# TopPanelV3_2.net
KiCad netlist of a schematic drawn in EAGLE
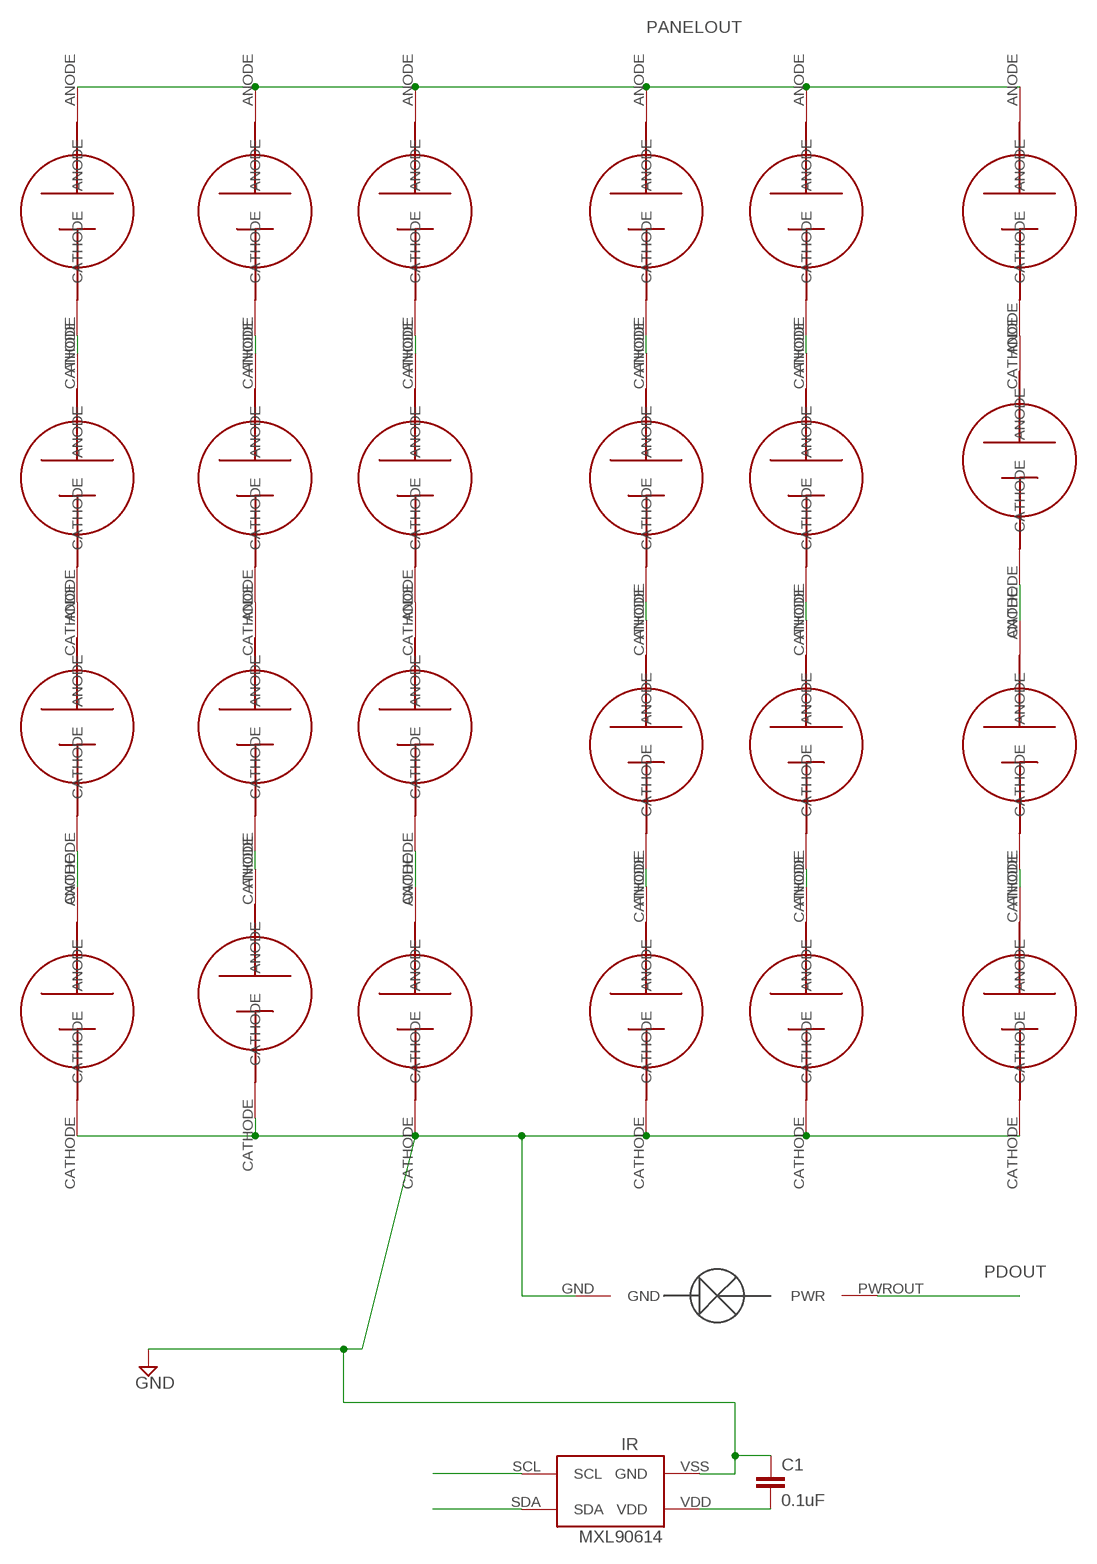
[diagram p0: schematic, sheet 1]

(export (version "E")
  (design (tool "Eeschema 10.0.6"))
  (components
    (comp (ref "1A")
      (value "SOLARCELL")
      (footprint "eagle-import:SOLARCELL")
      (libsource (lib "eagle-import") (part "SOLARCELL"))
    )
    (comp (ref "1B")
      (value "SOLARCELL")
      (footprint "eagle-import:SOLARCELL")
      (libsource (lib "eagle-import") (part "SOLARCELL"))
    )
    (comp (ref "1C")
      (value "SOLARCELL")
      (footprint "eagle-import:SOLARCELL")
      (libsource (lib "eagle-import") (part "SOLARCELL"))
    )
    (comp (ref "1D")
      (value "SOLARCELL")
      (footprint "eagle-import:SOLARCELL")
      (libsource (lib "eagle-import") (part "SOLARCELL"))
    )
    (comp (ref "2A")
      (value "SOLARCELL")
      (footprint "eagle-import:SOLARCELL")
      (libsource (lib "eagle-import") (part "SOLARCELL"))
    )
    (comp (ref "2B")
      (value "SOLARCELL")
      (footprint "eagle-import:SOLARCELL")
      (libsource (lib "eagle-import") (part "SOLARCELL"))
    )
    (comp (ref "2C")
      (value "SOLARCELL")
      (footprint "eagle-import:SOLARCELL")
      (libsource (lib "eagle-import") (part "SOLARCELL"))
    )
    (comp (ref "2D")
      (value "SOLARCELL")
      (footprint "eagle-import:SOLARCELL")
      (libsource (lib "eagle-import") (part "SOLARCELL"))
    )
    (comp (ref "3A")
      (value "SOLARCELL")
      (footprint "eagle-import:SOLARCELL")
      (libsource (lib "eagle-import") (part "SOLARCELL"))
    )
    (comp (ref "3B")
      (value "SOLARCELL")
      (footprint "eagle-import:SOLARCELL")
      (libsource (lib "eagle-import") (part "SOLARCELL"))
    )
    (comp (ref "3C")
      (value "SOLARCELL")
      (footprint "eagle-import:SOLARCELL")
      (libsource (lib "eagle-import") (part "SOLARCELL"))
    )
    (comp (ref "3D")
      (value "SOLARCELL")
      (footprint "eagle-import:SOLARCELL")
      (libsource (lib "eagle-import") (part "SOLARCELL"))
    )
    (comp (ref "4A")
      (value "SOLARCELL")
      (footprint "eagle-import:SOLARCELL")
      (libsource (lib "eagle-import") (part "SOLARCELL"))
    )
    (comp (ref "4B")
      (value "SOLARCELL")
      (footprint "eagle-import:SOLARCELL")
      (libsource (lib "eagle-import") (part "SOLARCELL"))
    )
    (comp (ref "4C")
      (value "SOLARCELL")
      (footprint "eagle-import:SOLARCELL")
      (libsource (lib "eagle-import") (part "SOLARCELL"))
    )
    (comp (ref "4D")
      (value "SOLARCELL")
      (footprint "eagle-import:SOLARCELL")
      (libsource (lib "eagle-import") (part "SOLARCELL"))
    )
    (comp (ref "5A")
      (value "SOLARCELL")
      (footprint "eagle-import:SOLARCELL")
      (libsource (lib "eagle-import") (part "SOLARCELL"))
    )
    (comp (ref "5B")
      (value "SOLARCELL")
      (footprint "eagle-import:SOLARCELL")
      (libsource (lib "eagle-import") (part "SOLARCELL"))
    )
    (comp (ref "5C")
      (value "SOLARCELL")
      (footprint "eagle-import:SOLARCELL")
      (libsource (lib "eagle-import") (part "SOLARCELL"))
    )
    (comp (ref "5D")
      (value "SOLARCELL")
      (footprint "eagle-import:SOLARCELL")
      (libsource (lib "eagle-import") (part "SOLARCELL"))
    )
    (comp (ref "6A")
      (value "SOLARCELL")
      (footprint "eagle-import:SOLARCELL")
      (libsource (lib "eagle-import") (part "SOLARCELL"))
    )
    (comp (ref "6B")
      (value "SOLARCELL")
      (footprint "eagle-import:SOLARCELL")
      (libsource (lib "eagle-import") (part "SOLARCELL"))
    )
    (comp (ref "6C")
      (value "SOLARCELL")
      (footprint "eagle-import:SOLARCELL")
      (libsource (lib "eagle-import") (part "SOLARCELL"))
    )
    (comp (ref "6D")
      (value "SOLARCELL")
      (footprint "eagle-import:SOLARCELL")
      (libsource (lib "eagle-import") (part "SOLARCELL"))
    )
    (comp (ref "C1")
      (value "0.1uF")
      (footprint "eagle-import:0805")
      (libsource (lib "eagle-import") (part "CAP0805"))
    )
    (comp (ref "IR")
      (value "MXL90620")
      (footprint "eagle-import:MXL90614")
      (libsource (lib "eagle-import") (part "MXL90620"))
    )
    (comp (ref "U$1")
      (value "PHOTODETECTOR")
      (footprint "eagle-import:PHOTODECTORDEVICE2")
      (libsource (lib "eagle-import") (part "PHOTODETECTOR"))
    )
  )
  (nets
    (net (code "1") (name "/PANELOUT") (class "Default")
      (node (ref "1A") (pin "ANODE") (pinfunction "ANODE_ANODE") (pintype "bidirectional"))
      (node (ref "2A") (pin "ANODE") (pinfunction "ANODE_ANODE") (pintype "bidirectional"))
      (node (ref "3A") (pin "ANODE") (pinfunction "ANODE_ANODE") (pintype "bidirectional"))
      (node (ref "4A") (pin "ANODE") (pinfunction "ANODE_ANODE") (pintype "bidirectional"))
      (node (ref "5A") (pin "ANODE") (pinfunction "ANODE_ANODE") (pintype "bidirectional"))
      (node (ref "6A") (pin "ANODE") (pinfunction "ANODE_ANODE") (pintype "bidirectional"))
    )
    (net (code "2") (name "/PDOUT") (class "Default")
      (node (ref "U$1") (pin "PWROUT") (pinfunction "PWR_PWROUT") (pintype "bidirectional"))
    )
    (net (code "3") (name "GND") (class "Default")
      (node (ref "1D") (pin "CATHODE") (pinfunction "CATHODE_CATHODE") (pintype "bidirectional"))
      (node (ref "2D") (pin "CATHODE") (pinfunction "CATHODE_CATHODE") (pintype "bidirectional"))
      (node (ref "3D") (pin "CATHODE") (pinfunction "CATHODE_CATHODE") (pintype "bidirectional"))
      (node (ref "4D") (pin "CATHODE") (pinfunction "CATHODE_CATHODE") (pintype "bidirectional"))
      (node (ref "5D") (pin "CATHODE") (pinfunction "CATHODE_CATHODE") (pintype "bidirectional"))
      (node (ref "6D") (pin "CATHODE") (pinfunction "CATHODE_CATHODE") (pintype "bidirectional"))
      (node (ref "C1") (pin "1") (pinfunction "1_1") (pintype "passive"))
      (node (ref "IR") (pin "VSS") (pinfunction "GND_VSS") (pintype "bidirectional"))
      (node (ref "U$1") (pin "GND") (pinfunction "GND_GND") (pintype "bidirectional"))
    )
    (net (code "4") (name "Net-(1A-PadCATHODE)") (class "Default")
      (node (ref "1A") (pin "CATHODE") (pinfunction "CATHODE_CATHODE") (pintype "bidirectional"))
      (node (ref "1B") (pin "ANODE") (pinfunction "ANODE_ANODE") (pintype "bidirectional"))
    )
    (net (code "5") (name "Net-(1B-PadCATHODE)") (class "Default")
      (node (ref "1B") (pin "CATHODE") (pinfunction "CATHODE_CATHODE") (pintype "bidirectional"))
      (node (ref "1C") (pin "ANODE") (pinfunction "ANODE_ANODE") (pintype "bidirectional"))
    )
    (net (code "6") (name "Net-(1C-PadCATHODE)") (class "Default")
      (node (ref "1C") (pin "CATHODE") (pinfunction "CATHODE_CATHODE") (pintype "bidirectional"))
      (node (ref "1D") (pin "ANODE") (pinfunction "ANODE_ANODE") (pintype "bidirectional"))
    )
    (net (code "7") (name "Net-(2A-PadCATHODE)") (class "Default")
      (node (ref "2A") (pin "CATHODE") (pinfunction "CATHODE_CATHODE") (pintype "bidirectional"))
      (node (ref "2B") (pin "ANODE") (pinfunction "ANODE_ANODE") (pintype "bidirectional"))
    )
    (net (code "8") (name "Net-(2B-PadCATHODE)") (class "Default")
      (node (ref "2B") (pin "CATHODE") (pinfunction "CATHODE_CATHODE") (pintype "bidirectional"))
      (node (ref "2C") (pin "ANODE") (pinfunction "ANODE_ANODE") (pintype "bidirectional"))
    )
    (net (code "9") (name "Net-(2C-PadCATHODE)") (class "Default")
      (node (ref "2C") (pin "CATHODE") (pinfunction "CATHODE_CATHODE") (pintype "bidirectional"))
      (node (ref "2D") (pin "ANODE") (pinfunction "ANODE_ANODE") (pintype "bidirectional"))
    )
    (net (code "10") (name "Net-(3A-PadCATHODE)") (class "Default")
      (node (ref "3A") (pin "CATHODE") (pinfunction "CATHODE_CATHODE") (pintype "bidirectional"))
      (node (ref "3B") (pin "ANODE") (pinfunction "ANODE_ANODE") (pintype "bidirectional"))
    )
    (net (code "11") (name "Net-(3B-PadCATHODE)") (class "Default")
      (node (ref "3B") (pin "CATHODE") (pinfunction "CATHODE_CATHODE") (pintype "bidirectional"))
      (node (ref "3C") (pin "ANODE") (pinfunction "ANODE_ANODE") (pintype "bidirectional"))
    )
    (net (code "12") (name "Net-(3C-PadCATHODE)") (class "Default")
      (node (ref "3C") (pin "CATHODE") (pinfunction "CATHODE_CATHODE") (pintype "bidirectional"))
      (node (ref "3D") (pin "ANODE") (pinfunction "ANODE_ANODE") (pintype "bidirectional"))
    )
    (net (code "13") (name "Net-(4A-PadCATHODE)") (class "Default")
      (node (ref "4A") (pin "CATHODE") (pinfunction "CATHODE_CATHODE") (pintype "bidirectional"))
      (node (ref "4B") (pin "ANODE") (pinfunction "ANODE_ANODE") (pintype "bidirectional"))
    )
    (net (code "14") (name "Net-(4B-PadCATHODE)") (class "Default")
      (node (ref "4B") (pin "CATHODE") (pinfunction "CATHODE_CATHODE") (pintype "bidirectional"))
      (node (ref "4C") (pin "ANODE") (pinfunction "ANODE_ANODE") (pintype "bidirectional"))
    )
    (net (code "15") (name "Net-(4C-PadCATHODE)") (class "Default")
      (node (ref "4C") (pin "CATHODE") (pinfunction "CATHODE_CATHODE") (pintype "bidirectional"))
      (node (ref "4D") (pin "ANODE") (pinfunction "ANODE_ANODE") (pintype "bidirectional"))
    )
    (net (code "16") (name "Net-(5A-PadCATHODE)") (class "Default")
      (node (ref "5A") (pin "CATHODE") (pinfunction "CATHODE_CATHODE") (pintype "bidirectional"))
      (node (ref "5B") (pin "ANODE") (pinfunction "ANODE_ANODE") (pintype "bidirectional"))
    )
    (net (code "17") (name "Net-(5B-PadCATHODE)") (class "Default")
      (node (ref "5B") (pin "CATHODE") (pinfunction "CATHODE_CATHODE") (pintype "bidirectional"))
      (node (ref "5C") (pin "ANODE") (pinfunction "ANODE_ANODE") (pintype "bidirectional"))
    )
    (net (code "18") (name "Net-(5C-PadCATHODE)") (class "Default")
      (node (ref "5C") (pin "CATHODE") (pinfunction "CATHODE_CATHODE") (pintype "bidirectional"))
      (node (ref "5D") (pin "ANODE") (pinfunction "ANODE_ANODE") (pintype "bidirectional"))
    )
    (net (code "19") (name "Net-(6A-PadCATHODE)") (class "Default")
      (node (ref "6A") (pin "CATHODE") (pinfunction "CATHODE_CATHODE") (pintype "bidirectional"))
      (node (ref "6B") (pin "ANODE") (pinfunction "ANODE_ANODE") (pintype "bidirectional"))
    )
    (net (code "20") (name "Net-(6B-PadCATHODE)") (class "Default")
      (node (ref "6B") (pin "CATHODE") (pinfunction "CATHODE_CATHODE") (pintype "bidirectional"))
      (node (ref "6C") (pin "ANODE") (pinfunction "ANODE_ANODE") (pintype "bidirectional"))
    )
    (net (code "21") (name "Net-(6C-PadCATHODE)") (class "Default")
      (node (ref "6C") (pin "CATHODE") (pinfunction "CATHODE_CATHODE") (pintype "bidirectional"))
      (node (ref "6D") (pin "ANODE") (pinfunction "ANODE_ANODE") (pintype "bidirectional"))
    )
    (net (code "22") (name "Net-(C1-Pad2)") (class "Default")
      (node (ref "C1") (pin "2") (pinfunction "2_2") (pintype "passive"))
      (node (ref "IR") (pin "VDD") (pinfunction "VDD_VDD") (pintype "bidirectional"))
    )
    (net (code "23") (name "unconnected-(IR-PadSCL)") (class "Default")
      (node (ref "IR") (pin "SCL") (pinfunction "SCL_SCL") (pintype "bidirectional"))
    )
    (net (code "24") (name "unconnected-(IR-PadSDA)") (class "Default")
      (node (ref "IR") (pin "SDA") (pinfunction "SDA_SDA") (pintype "bidirectional"))
    )
  )
)
